# 2_waffling60-MX_matrix.net
KiCad netlist of a schematic drawn in Altium Designer
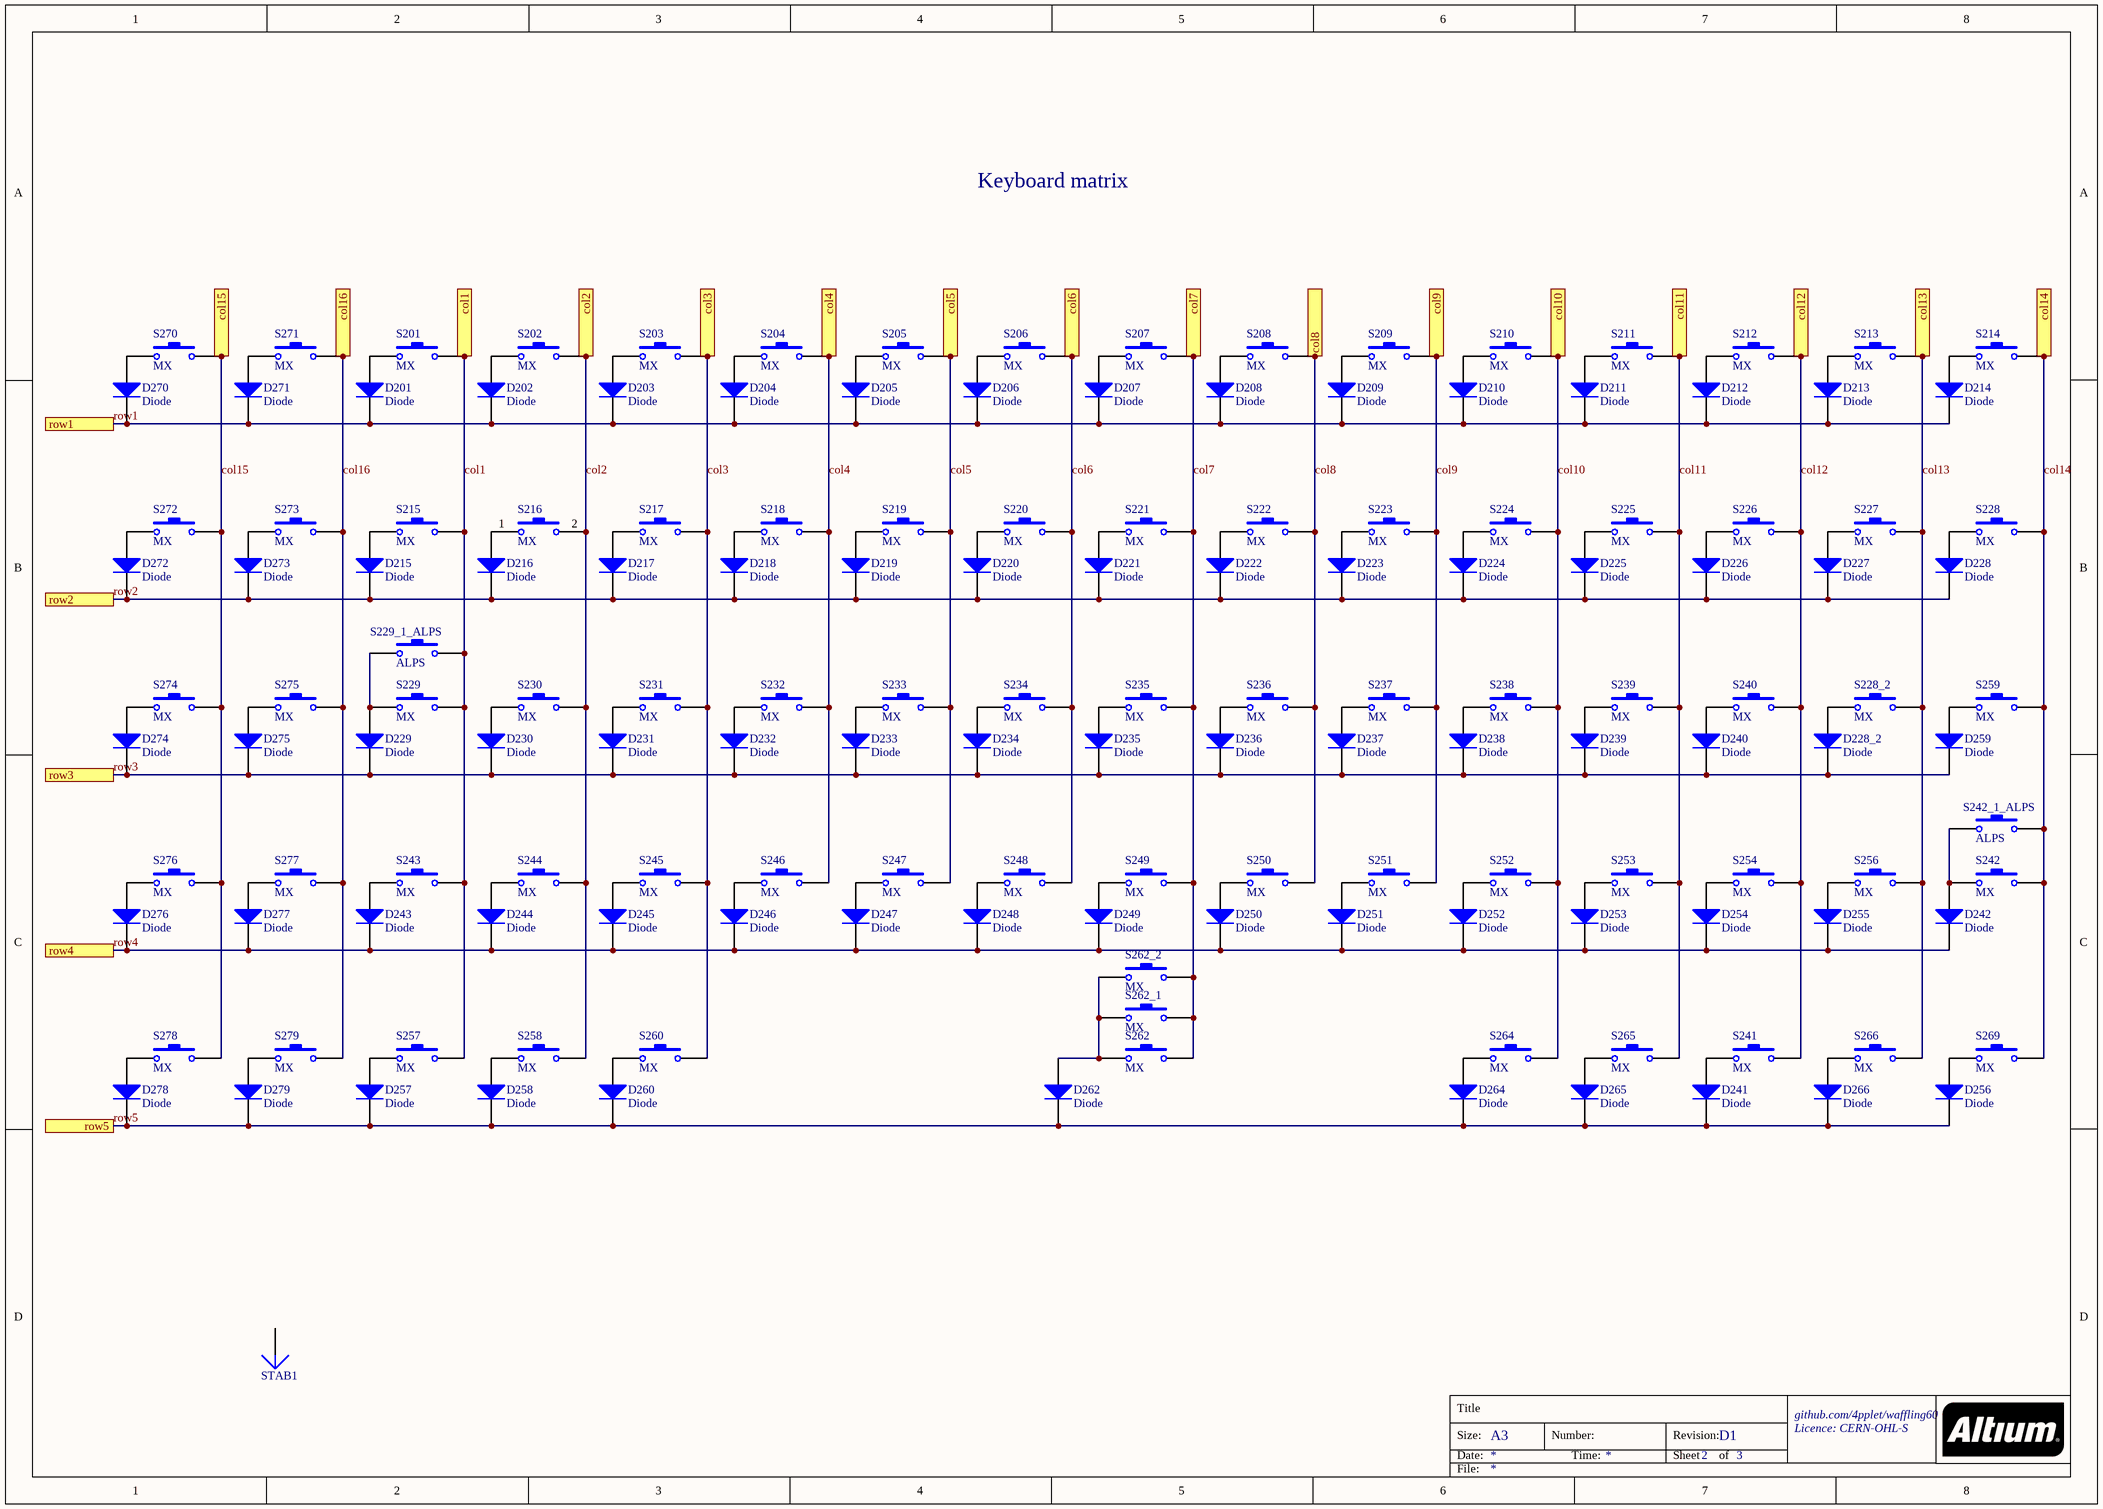
[diagram p0: 2_waffling60-MX_matrix.SchDoc]

(export (version "E")
  (design (tool "Eeschema 10.0.6"))
  (components
    (comp (ref "D201")
      (value "Diode")
      (footprint "SOD-123")
      (description "Default Diode")
      (fields (field (name "LCSC PART #") "C81598") (field (name "MRF.PART") "1N4148W"))
      (libsource (lib "Miscellaneous Devices") (part "Diode"))
    )
    (comp (ref "D202")
      (value "Diode")
      (footprint "SOD-123")
      (description "Default Diode")
      (fields (field (name "LCSC PART #") "C81598") (field (name "MRF.PART") "1N4148W"))
      (libsource (lib "Miscellaneous Devices") (part "Diode"))
    )
    (comp (ref "D203")
      (value "Diode")
      (footprint "SOD-123")
      (description "Default Diode")
      (fields (field (name "LCSC PART #") "C81598") (field (name "MRF.PART") "1N4148W"))
      (libsource (lib "Miscellaneous Devices") (part "Diode"))
    )
    (comp (ref "D204")
      (value "Diode")
      (footprint "SOD-123")
      (description "Default Diode")
      (fields (field (name "LCSC PART #") "C81598") (field (name "MRF.PART") "1N4148W"))
      (libsource (lib "Miscellaneous Devices") (part "Diode"))
    )
    (comp (ref "D205")
      (value "Diode")
      (footprint "SOD-123")
      (description "Default Diode")
      (fields (field (name "LCSC PART #") "C81598") (field (name "MRF.PART") "1N4148W"))
      (libsource (lib "Miscellaneous Devices") (part "Diode"))
    )
    (comp (ref "D206")
      (value "Diode")
      (footprint "SOD-123")
      (description "Default Diode")
      (fields (field (name "LCSC PART #") "C81598") (field (name "MRF.PART") "1N4148W"))
      (libsource (lib "Miscellaneous Devices") (part "Diode"))
    )
    (comp (ref "D207")
      (value "Diode")
      (footprint "SOD-123")
      (description "Default Diode")
      (fields (field (name "LCSC PART #") "C81598") (field (name "MRF.PART") "1N4148W"))
      (libsource (lib "Miscellaneous Devices") (part "Diode"))
    )
    (comp (ref "D208")
      (value "Diode")
      (footprint "SOD-123")
      (description "Default Diode")
      (fields (field (name "LCSC PART #") "C81598") (field (name "MRF.PART") "1N4148W"))
      (libsource (lib "Miscellaneous Devices") (part "Diode"))
    )
    (comp (ref "D209")
      (value "Diode")
      (footprint "SOD-123")
      (description "Default Diode")
      (fields (field (name "LCSC PART #") "C81598") (field (name "MRF.PART") "1N4148W"))
      (libsource (lib "Miscellaneous Devices") (part "Diode"))
    )
    (comp (ref "D210")
      (value "Diode")
      (footprint "SOD-123")
      (description "Default Diode")
      (fields (field (name "LCSC PART #") "C81598") (field (name "MRF.PART") "1N4148W"))
      (libsource (lib "Miscellaneous Devices") (part "Diode"))
    )
    (comp (ref "D211")
      (value "Diode")
      (footprint "SOD-123")
      (description "Default Diode")
      (fields (field (name "LCSC PART #") "C81598") (field (name "MRF.PART") "1N4148W"))
      (libsource (lib "Miscellaneous Devices") (part "Diode"))
    )
    (comp (ref "D212")
      (value "Diode")
      (footprint "SOD-123")
      (description "Default Diode")
      (fields (field (name "LCSC PART #") "C81598") (field (name "MRF.PART") "1N4148W"))
      (libsource (lib "Miscellaneous Devices") (part "Diode"))
    )
    (comp (ref "D213")
      (value "Diode")
      (footprint "SOD-123")
      (description "Default Diode")
      (fields (field (name "LCSC PART #") "C81598") (field (name "MRF.PART") "1N4148W"))
      (libsource (lib "Miscellaneous Devices") (part "Diode"))
    )
    (comp (ref "D214")
      (value "Diode")
      (footprint "SOD-123")
      (description "Default Diode")
      (fields (field (name "LCSC PART #") "C81598") (field (name "MRF.PART") "1N4148W"))
      (libsource (lib "Miscellaneous Devices") (part "Diode"))
    )
    (comp (ref "D215")
      (value "Diode")
      (footprint "SOD-123")
      (description "Default Diode")
      (fields (field (name "LCSC PART #") "C81598") (field (name "MRF.PART") "1N4148W"))
      (libsource (lib "Miscellaneous Devices") (part "Diode"))
    )
    (comp (ref "D216")
      (value "Diode")
      (footprint "SOD-123")
      (description "Default Diode")
      (fields (field (name "LCSC PART #") "C81598") (field (name "MRF.PART") "1N4148W"))
      (libsource (lib "Miscellaneous Devices") (part "Diode"))
    )
    (comp (ref "D217")
      (value "Diode")
      (footprint "SOD-123")
      (description "Default Diode")
      (fields (field (name "LCSC PART #") "C81598") (field (name "MRF.PART") "1N4148W"))
      (libsource (lib "Miscellaneous Devices") (part "Diode"))
    )
    (comp (ref "D218")
      (value "Diode")
      (footprint "SOD-123")
      (description "Default Diode")
      (fields (field (name "LCSC PART #") "C81598") (field (name "MRF.PART") "1N4148W"))
      (libsource (lib "Miscellaneous Devices") (part "Diode"))
    )
    (comp (ref "D219")
      (value "Diode")
      (footprint "SOD-123")
      (description "Default Diode")
      (fields (field (name "LCSC PART #") "C81598") (field (name "MRF.PART") "1N4148W"))
      (libsource (lib "Miscellaneous Devices") (part "Diode"))
    )
    (comp (ref "D220")
      (value "Diode")
      (footprint "SOD-123")
      (description "Default Diode")
      (fields (field (name "LCSC PART #") "C81598") (field (name "MRF.PART") "1N4148W"))
      (libsource (lib "Miscellaneous Devices") (part "Diode"))
    )
    (comp (ref "D221")
      (value "Diode")
      (footprint "SOD-123")
      (description "Default Diode")
      (fields (field (name "LCSC PART #") "C81598") (field (name "MRF.PART") "1N4148W"))
      (libsource (lib "Miscellaneous Devices") (part "Diode"))
    )
    (comp (ref "D222")
      (value "Diode")
      (footprint "SOD-123")
      (description "Default Diode")
      (fields (field (name "LCSC PART #") "C81598") (field (name "MRF.PART") "1N4148W"))
      (libsource (lib "Miscellaneous Devices") (part "Diode"))
    )
    (comp (ref "D223")
      (value "Diode")
      (footprint "SOD-123")
      (description "Default Diode")
      (fields (field (name "LCSC PART #") "C81598") (field (name "MRF.PART") "1N4148W"))
      (libsource (lib "Miscellaneous Devices") (part "Diode"))
    )
    (comp (ref "D224")
      (value "Diode")
      (footprint "SOD-123")
      (description "Default Diode")
      (fields (field (name "LCSC PART #") "C81598") (field (name "MRF.PART") "1N4148W"))
      (libsource (lib "Miscellaneous Devices") (part "Diode"))
    )
    (comp (ref "D225")
      (value "Diode")
      (footprint "SOD-123")
      (description "Default Diode")
      (fields (field (name "LCSC PART #") "C81598") (field (name "MRF.PART") "1N4148W"))
      (libsource (lib "Miscellaneous Devices") (part "Diode"))
    )
    (comp (ref "D226")
      (value "Diode")
      (footprint "SOD-123")
      (description "Default Diode")
      (fields (field (name "LCSC PART #") "C81598") (field (name "MRF.PART") "1N4148W"))
      (libsource (lib "Miscellaneous Devices") (part "Diode"))
    )
    (comp (ref "D227")
      (value "Diode")
      (footprint "SOD-123")
      (description "Default Diode")
      (fields (field (name "LCSC PART #") "C81598") (field (name "MRF.PART") "1N4148W"))
      (libsource (lib "Miscellaneous Devices") (part "Diode"))
    )
    (comp (ref "D228")
      (value "Diode")
      (footprint "SOD-123")
      (description "Default Diode")
      (fields (field (name "LCSC PART #") "C81598") (field (name "MRF.PART") "1N4148W"))
      (libsource (lib "Miscellaneous Devices") (part "Diode"))
    )
    (comp (ref "D228_2")
      (value "Diode")
      (footprint "SOD-123")
      (description "Default Diode")
      (fields (field (name "LCSC PART #") "C81598") (field (name "MRF.PART") "1N4148W"))
      (libsource (lib "Miscellaneous Devices") (part "Diode"))
    )
    (comp (ref "D229")
      (value "Diode")
      (footprint "SOD-123")
      (description "Default Diode")
      (fields (field (name "LCSC PART #") "C81598") (field (name "MRF.PART") "1N4148W"))
      (libsource (lib "Miscellaneous Devices") (part "Diode"))
    )
    (comp (ref "D230")
      (value "Diode")
      (footprint "SOD-123")
      (description "Default Diode")
      (fields (field (name "LCSC PART #") "C81598") (field (name "MRF.PART") "1N4148W"))
      (libsource (lib "Miscellaneous Devices") (part "Diode"))
    )
    (comp (ref "D231")
      (value "Diode")
      (footprint "SOD-123")
      (description "Default Diode")
      (fields (field (name "LCSC PART #") "C81598") (field (name "MRF.PART") "1N4148W"))
      (libsource (lib "Miscellaneous Devices") (part "Diode"))
    )
    (comp (ref "D232")
      (value "Diode")
      (footprint "SOD-123")
      (description "Default Diode")
      (fields (field (name "LCSC PART #") "C81598") (field (name "MRF.PART") "1N4148W"))
      (libsource (lib "Miscellaneous Devices") (part "Diode"))
    )
    (comp (ref "D233")
      (value "Diode")
      (footprint "SOD-123")
      (description "Default Diode")
      (fields (field (name "LCSC PART #") "C81598") (field (name "MRF.PART") "1N4148W"))
      (libsource (lib "Miscellaneous Devices") (part "Diode"))
    )
    (comp (ref "D234")
      (value "Diode")
      (footprint "SOD-123")
      (description "Default Diode")
      (fields (field (name "LCSC PART #") "C81598") (field (name "MRF.PART") "1N4148W"))
      (libsource (lib "Miscellaneous Devices") (part "Diode"))
    )
    (comp (ref "D235")
      (value "Diode")
      (footprint "SOD-123")
      (description "Default Diode")
      (fields (field (name "LCSC PART #") "C81598") (field (name "MRF.PART") "1N4148W"))
      (libsource (lib "Miscellaneous Devices") (part "Diode"))
    )
    (comp (ref "D236")
      (value "Diode")
      (footprint "SOD-123")
      (description "Default Diode")
      (fields (field (name "LCSC PART #") "C81598") (field (name "MRF.PART") "1N4148W"))
      (libsource (lib "Miscellaneous Devices") (part "Diode"))
    )
    (comp (ref "D237")
      (value "Diode")
      (footprint "SOD-123")
      (description "Default Diode")
      (fields (field (name "LCSC PART #") "C81598") (field (name "MRF.PART") "1N4148W"))
      (libsource (lib "Miscellaneous Devices") (part "Diode"))
    )
    (comp (ref "D238")
      (value "Diode")
      (footprint "SOD-123")
      (description "Default Diode")
      (fields (field (name "LCSC PART #") "C81598") (field (name "MRF.PART") "1N4148W"))
      (libsource (lib "Miscellaneous Devices") (part "Diode"))
    )
    (comp (ref "D239")
      (value "Diode")
      (footprint "SOD-123")
      (description "Default Diode")
      (fields (field (name "LCSC PART #") "C81598") (field (name "MRF.PART") "1N4148W"))
      (libsource (lib "Miscellaneous Devices") (part "Diode"))
    )
    (comp (ref "D240")
      (value "Diode")
      (footprint "SOD-123")
      (description "Default Diode")
      (fields (field (name "LCSC PART #") "C81598") (field (name "MRF.PART") "1N4148W"))
      (libsource (lib "Miscellaneous Devices") (part "Diode"))
    )
    (comp (ref "D241")
      (value "Diode")
      (footprint "SOD-123")
      (description "Default Diode")
      (fields (field (name "LCSC PART #") "C81598") (field (name "MRF.PART") "1N4148W"))
      (libsource (lib "Miscellaneous Devices") (part "Diode"))
    )
    (comp (ref "D242")
      (value "Diode")
      (footprint "SOD-123")
      (description "Default Diode")
      (fields (field (name "LCSC PART #") "C81598") (field (name "MRF.PART") "1N4148W"))
      (libsource (lib "Miscellaneous Devices") (part "Diode"))
    )
    (comp (ref "D243")
      (value "Diode")
      (footprint "SOD-123")
      (description "Default Diode")
      (fields (field (name "LCSC PART #") "C81598") (field (name "MRF.PART") "1N4148W"))
      (libsource (lib "Miscellaneous Devices") (part "Diode"))
    )
    (comp (ref "D244")
      (value "Diode")
      (footprint "SOD-123")
      (description "Default Diode")
      (fields (field (name "LCSC PART #") "C81598") (field (name "MRF.PART") "1N4148W"))
      (libsource (lib "Miscellaneous Devices") (part "Diode"))
    )
    (comp (ref "D245")
      (value "Diode")
      (footprint "SOD-123")
      (description "Default Diode")
      (fields (field (name "LCSC PART #") "C81598") (field (name "MRF.PART") "1N4148W"))
      (libsource (lib "Miscellaneous Devices") (part "Diode"))
    )
    (comp (ref "D246")
      (value "Diode")
      (footprint "SOD-123")
      (description "Default Diode")
      (fields (field (name "LCSC PART #") "C81598") (field (name "MRF.PART") "1N4148W"))
      (libsource (lib "Miscellaneous Devices") (part "Diode"))
    )
    (comp (ref "D247")
      (value "Diode")
      (footprint "SOD-123")
      (description "Default Diode")
      (fields (field (name "LCSC PART #") "C81598") (field (name "MRF.PART") "1N4148W"))
      (libsource (lib "Miscellaneous Devices") (part "Diode"))
    )
    (comp (ref "D248")
      (value "Diode")
      (footprint "SOD-123")
      (description "Default Diode")
      (fields (field (name "LCSC PART #") "C81598") (field (name "MRF.PART") "1N4148W"))
      (libsource (lib "Miscellaneous Devices") (part "Diode"))
    )
    (comp (ref "D249")
      (value "Diode")
      (footprint "SOD-123")
      (description "Default Diode")
      (fields (field (name "LCSC PART #") "C81598") (field (name "MRF.PART") "1N4148W"))
      (libsource (lib "Miscellaneous Devices") (part "Diode"))
    )
    (comp (ref "D250")
      (value "Diode")
      (footprint "SOD-123")
      (description "Default Diode")
      (fields (field (name "LCSC PART #") "C81598") (field (name "MRF.PART") "1N4148W"))
      (libsource (lib "Miscellaneous Devices") (part "Diode"))
    )
    (comp (ref "D251")
      (value "Diode")
      (footprint "SOD-123")
      (description "Default Diode")
      (fields (field (name "LCSC PART #") "C81598") (field (name "MRF.PART") "1N4148W"))
      (libsource (lib "Miscellaneous Devices") (part "Diode"))
    )
    (comp (ref "D252")
      (value "Diode")
      (footprint "SOD-123")
      (description "Default Diode")
      (fields (field (name "LCSC PART #") "C81598") (field (name "MRF.PART") "1N4148W"))
      (libsource (lib "Miscellaneous Devices") (part "Diode"))
    )
    (comp (ref "D253")
      (value "Diode")
      (footprint "SOD-123")
      (description "Default Diode")
      (fields (field (name "LCSC PART #") "C81598") (field (name "MRF.PART") "1N4148W"))
      (libsource (lib "Miscellaneous Devices") (part "Diode"))
    )
    (comp (ref "D254")
      (value "Diode")
      (footprint "SOD-123")
      (description "Default Diode")
      (fields (field (name "LCSC PART #") "C81598") (field (name "MRF.PART") "1N4148W"))
      (libsource (lib "Miscellaneous Devices") (part "Diode"))
    )
    (comp (ref "D255")
      (value "Diode")
      (footprint "SOD-123")
      (description "Default Diode")
      (fields (field (name "LCSC PART #") "C81598") (field (name "MRF.PART") "1N4148W"))
      (libsource (lib "Miscellaneous Devices") (part "Diode"))
    )
    (comp (ref "D256")
      (value "Diode")
      (footprint "SOD-123")
      (description "Default Diode")
      (fields (field (name "LCSC PART #") "C81598") (field (name "MRF.PART") "1N4148W"))
      (libsource (lib "Miscellaneous Devices") (part "Diode"))
    )
    (comp (ref "D257")
      (value "Diode")
      (footprint "SOD-123")
      (description "Default Diode")
      (fields (field (name "LCSC PART #") "C81598") (field (name "MRF.PART") "1N4148W"))
      (libsource (lib "Miscellaneous Devices") (part "Diode"))
    )
    (comp (ref "D258")
      (value "Diode")
      (footprint "SOD-123")
      (description "Default Diode")
      (fields (field (name "LCSC PART #") "C81598") (field (name "MRF.PART") "1N4148W"))
      (libsource (lib "Miscellaneous Devices") (part "Diode"))
    )
    (comp (ref "D259")
      (value "Diode")
      (footprint "SOD-123")
      (description "Default Diode")
      (fields (field (name "LCSC PART #") "C81598") (field (name "MRF.PART") "1N4148W"))
      (libsource (lib "Miscellaneous Devices") (part "Diode"))
    )
    (comp (ref "D260")
      (value "Diode")
      (footprint "SOD-123")
      (description "Default Diode")
      (fields (field (name "LCSC PART #") "C81598") (field (name "MRF.PART") "1N4148W"))
      (libsource (lib "Miscellaneous Devices") (part "Diode"))
    )
    (comp (ref "D262")
      (value "Diode")
      (footprint "SOD-123")
      (description "Default Diode")
      (fields (field (name "LCSC PART #") "C81598") (field (name "MRF.PART") "1N4148W"))
      (libsource (lib "Miscellaneous Devices") (part "Diode"))
    )
    (comp (ref "D264")
      (value "Diode")
      (footprint "SOD-123")
      (description "Default Diode")
      (fields (field (name "LCSC PART #") "C81598") (field (name "MRF.PART") "1N4148W"))
      (libsource (lib "Miscellaneous Devices") (part "Diode"))
    )
    (comp (ref "D265")
      (value "Diode")
      (footprint "SOD-123")
      (description "Default Diode")
      (fields (field (name "LCSC PART #") "C81598") (field (name "MRF.PART") "1N4148W"))
      (libsource (lib "Miscellaneous Devices") (part "Diode"))
    )
    (comp (ref "D266")
      (value "Diode")
      (footprint "SOD-123")
      (description "Default Diode")
      (fields (field (name "LCSC PART #") "C81598") (field (name "MRF.PART") "1N4148W"))
      (libsource (lib "Miscellaneous Devices") (part "Diode"))
    )
    (comp (ref "D270")
      (value "Diode")
      (footprint "SOD-123")
      (description "Default Diode")
      (fields (field (name "LCSC PART #") "C81598") (field (name "MRF.PART") "1N4148W"))
      (libsource (lib "Miscellaneous Devices") (part "Diode"))
    )
    (comp (ref "D271")
      (value "Diode")
      (footprint "SOD-123")
      (description "Default Diode")
      (fields (field (name "LCSC PART #") "C81598") (field (name "MRF.PART") "1N4148W"))
      (libsource (lib "Miscellaneous Devices") (part "Diode"))
    )
    (comp (ref "D272")
      (value "Diode")
      (footprint "SOD-123")
      (description "Default Diode")
      (fields (field (name "LCSC PART #") "C81598") (field (name "MRF.PART") "1N4148W"))
      (libsource (lib "Miscellaneous Devices") (part "Diode"))
    )
    (comp (ref "D273")
      (value "Diode")
      (footprint "SOD-123")
      (description "Default Diode")
      (fields (field (name "LCSC PART #") "C81598") (field (name "MRF.PART") "1N4148W"))
      (libsource (lib "Miscellaneous Devices") (part "Diode"))
    )
    (comp (ref "D274")
      (value "Diode")
      (footprint "SOD-123")
      (description "Default Diode")
      (fields (field (name "LCSC PART #") "C81598") (field (name "MRF.PART") "1N4148W"))
      (libsource (lib "Miscellaneous Devices") (part "Diode"))
    )
    (comp (ref "D275")
      (value "Diode")
      (footprint "SOD-123")
      (description "Default Diode")
      (fields (field (name "LCSC PART #") "C81598") (field (name "MRF.PART") "1N4148W"))
      (libsource (lib "Miscellaneous Devices") (part "Diode"))
    )
    (comp (ref "D276")
      (value "Diode")
      (footprint "SOD-123")
      (description "Default Diode")
      (fields (field (name "LCSC PART #") "C81598") (field (name "MRF.PART") "1N4148W"))
      (libsource (lib "Miscellaneous Devices") (part "Diode"))
    )
    (comp (ref "D277")
      (value "Diode")
      (footprint "SOD-123")
      (description "Default Diode")
      (fields (field (name "LCSC PART #") "C81598") (field (name "MRF.PART") "1N4148W"))
      (libsource (lib "Miscellaneous Devices") (part "Diode"))
    )
    (comp (ref "D278")
      (value "Diode")
      (footprint "SOD-123")
      (description "Default Diode")
      (fields (field (name "LCSC PART #") "C81598") (field (name "MRF.PART") "1N4148W"))
      (libsource (lib "Miscellaneous Devices") (part "Diode"))
    )
    (comp (ref "D279")
      (value "Diode")
      (footprint "SOD-123")
      (description "Default Diode")
      (fields (field (name "LCSC PART #") "C81598") (field (name "MRF.PART") "1N4148W"))
      (libsource (lib "Miscellaneous Devices") (part "Diode"))
    )
    (comp (ref "S201")
      (value "MX")
      (footprint "MX_ALPS-switch switched pol")
      (description "Switch")
      (libsource (lib "Miscellaneous Devices") (part "SW-PB"))
    )
    (comp (ref "S202")
      (value "MX")
      (footprint "MX_ALPS-switch - duplicate")
      (description "Switch")
      (libsource (lib "") (part "SW-PB_1"))
    )
    (comp (ref "S203")
      (value "MX")
      (footprint "MX_ALPS-switch switched pol")
      (description "Switch")
      (libsource (lib "Miscellaneous Devices") (part "SW-PB"))
    )
    (comp (ref "S204")
      (value "MX")
      (footprint "MX_ALPS-switch switched pol")
      (description "Switch")
      (libsource (lib "Miscellaneous Devices") (part "SW-PB"))
    )
    (comp (ref "S205")
      (value "MX")
      (footprint "MX_ALPS-switch switched pol")
      (description "Switch")
      (libsource (lib "Miscellaneous Devices") (part "SW-PB"))
    )
    (comp (ref "S206")
      (value "MX")
      (footprint "MX_ALPS-switch switched pol")
      (description "Switch")
      (libsource (lib "Miscellaneous Devices") (part "SW-PB"))
    )
    (comp (ref "S207")
      (value "MX")
      (footprint "MX_ALPS-switch switched pol")
      (description "Switch")
      (libsource (lib "Miscellaneous Devices") (part "SW-PB"))
    )
    (comp (ref "S208")
      (value "MX")
      (footprint "MX_ALPS-switch switched pol")
      (description "Switch")
      (libsource (lib "Miscellaneous Devices") (part "SW-PB"))
    )
    (comp (ref "S209")
      (value "MX")
      (footprint "MX_ALPS-switch switched pol")
      (description "Switch")
      (libsource (lib "Miscellaneous Devices") (part "SW-PB"))
    )
    (comp (ref "S210")
      (value "MX")
      (footprint "MX_ALPS-switch switched pol")
      (description "Switch")
      (libsource (lib "Miscellaneous Devices") (part "SW-PB"))
    )
    (comp (ref "S211")
      (value "MX")
      (footprint "MX_ALPS-switch switched pol")
      (description "Switch")
      (libsource (lib "Miscellaneous Devices") (part "SW-PB"))
    )
    (comp (ref "S212")
      (value "MX")
      (footprint "MX_ALPS-switch switched pol")
      (description "Switch")
      (libsource (lib "Miscellaneous Devices") (part "SW-PB"))
    )
    (comp (ref "S213")
      (value "MX")
      (footprint "MX_ALPS-switch switched pol")
      (description "Switch")
      (libsource (lib "Miscellaneous Devices") (part "SW-PB"))
    )
    (comp (ref "S214")
      (value "MX")
      (footprint "MX_ALPS-switch - duplicate")
      (description "Switch")
      (libsource (lib "Miscellaneous Devices") (part "SW-PB"))
    )
    (comp (ref "S215")
      (value "MX")
      (footprint "MX_ALPS-switch switched pol")
      (description "TAB")
      (libsource (lib "Miscellaneous Devices") (part "SW-PB"))
    )
    (comp (ref "S216")
      (value "MX")
      (footprint "MX_ALPS-switch - duplicate")
      (description "Switch")
      (libsource (lib "") (part "SW-PB_2"))
    )
    (comp (ref "S217")
      (value "MX")
      (footprint "MX_ALPS-switch switched pol")
      (description "Switch")
      (libsource (lib "Miscellaneous Devices") (part "SW-PB"))
    )
    (comp (ref "S218")
      (value "MX")
      (footprint "MX_ALPS-switch switched pol")
      (description "Switch")
      (libsource (lib "Miscellaneous Devices") (part "SW-PB"))
    )
    (comp (ref "S219")
      (value "MX")
      (footprint "MX_ALPS-switch switched pol")
      (description "Switch")
      (libsource (lib "Miscellaneous Devices") (part "SW-PB"))
    )
    (comp (ref "S220")
      (value "MX")
      (footprint "MX_ALPS-switch - duplicate")
      (description "Switch")
      (libsource (lib "Miscellaneous Devices") (part "SW-PB"))
    )
    (comp (ref "S221")
      (value "MX")
      (footprint "MX_ALPS-switch switched pol")
      (description "Switch")
      (libsource (lib "Miscellaneous Devices") (part "SW-PB"))
    )
    (comp (ref "S222")
      (value "MX")
      (footprint "MX_ALPS-switch - duplicate")
      (description "Switch")
      (libsource (lib "Miscellaneous Devices") (part "SW-PB"))
    )
    (comp (ref "S223")
      (value "MX")
      (footprint "MX_ALPS-switch switched pol")
      (description "Switch")
      (libsource (lib "Miscellaneous Devices") (part "SW-PB"))
    )
    (comp (ref "S224")
      (value "MX")
      (footprint "MX_ALPS-switch switched pol")
      (description "Switch")
      (libsource (lib "Miscellaneous Devices") (part "SW-PB"))
    )
    (comp (ref "S225")
      (value "MX")
      (footprint "MX_ALPS-switch switched pol")
      (description "Switch")
      (libsource (lib "Miscellaneous Devices") (part "SW-PB"))
    )
    (comp (ref "S226")
      (value "MX")
      (footprint "MX_ALPS-switch - duplicate")
      (description "Switch")
      (libsource (lib "Miscellaneous Devices") (part "SW-PB"))
    )
    (comp (ref "S227")
      (value "MX")
      (footprint "MX_ALPS-switch - duplicate")
      (description "Switch")
      (libsource (lib "Miscellaneous Devices") (part "SW-PB"))
    )
    (comp (ref "S228")
      (value "MX")
      (footprint "mx_alps - 1.5U")
      (description "Switch")
      (libsource (lib "Miscellaneous Devices") (part "SW-PB"))
    )
    (comp (ref "S228_2")
      (value "MX")
      (footprint "MX_ALPS-switch - duplicate")
      (description "Switch")
      (libsource (lib "Miscellaneous Devices") (part "SW-PB"))
    )
    (comp (ref "S229")
      (value "MX")
      (footprint "mx_alps - CAPS")
      (description "Switch")
      (libsource (lib "Miscellaneous Devices") (part "SW-PB"))
    )
    (comp (ref "S229_1_ALPS")
      (value "ALPS")
      (footprint "ALPS-switch - 1.5U")
      (description "Switch")
      (libsource (lib "Miscellaneous Devices") (part "SW-PB"))
    )
    (comp (ref "S230")
      (value "MX")
      (footprint "MX_ALPS-switch - duplicate")
      (description "Switch")
      (libsource (lib "Miscellaneous Devices") (part "SW-PB"))
    )
    (comp (ref "S231")
      (value "MX")
      (footprint "MX_ALPS-switch switched pol")
      (description "Switch")
      (libsource (lib "Miscellaneous Devices") (part "SW-PB"))
    )
    (comp (ref "S232")
      (value "MX")
      (footprint "MX_ALPS-switch switched pol")
      (description "Switch")
      (libsource (lib "Miscellaneous Devices") (part "SW-PB"))
    )
    (comp (ref "S233")
      (value "MX")
      (footprint "MX_ALPS-switch switched pol")
      (description "Switch")
      (libsource (lib "Miscellaneous Devices") (part "SW-PB"))
    )
    (comp (ref "S234")
      (value "MX")
      (footprint "MX_ALPS-switch switched pol")
      (description "Switch")
      (libsource (lib "Miscellaneous Devices") (part "SW-PB"))
    )
    (comp (ref "S235")
      (value "MX")
      (footprint "MX_ALPS-switch switched pol")
      (description "Switch")
      (libsource (lib "Miscellaneous Devices") (part "SW-PB"))
    )
    (comp (ref "S236")
      (value "MX")
      (footprint "MX_ALPS-switch switched pol")
      (description "Switch")
      (libsource (lib "Miscellaneous Devices") (part "SW-PB"))
    )
    (comp (ref "S237")
      (value "MX")
      (footprint "MX_ALPS-switch switched pol")
      (description "Switch")
      (libsource (lib "Miscellaneous Devices") (part "SW-PB"))
    )
    (comp (ref "S238")
      (value "MX")
      (footprint "MX_ALPS-switch switched pol")
      (description "Switch")
      (libsource (lib "Miscellaneous Devices") (part "SW-PB"))
    )
    (comp (ref "S239")
      (value "MX")
      (footprint "MX_ALPS-switch switched pol")
      (description "Switch")
      (libsource (lib "Miscellaneous Devices") (part "SW-PB"))
    )
    (comp (ref "S240")
      (value "MX")
      (footprint "MX_ALPS-switch switched pol")
      (description "Switch")
      (libsource (lib "Miscellaneous Devices") (part "SW-PB"))
    )
    (comp (ref "S241")
      (value "MX")
      (footprint "mx_alps - 1u MOD-R")
      (description "Switch")
      (libsource (lib "Miscellaneous Devices") (part "SW-PB"))
    )
    (comp (ref "S242")
      (value "MX")
      (footprint "mx_alps - Enter - Rotated Stab")
      (description "Switch")
      (libsource (lib "Miscellaneous Devices") (part "SW-PB"))
    )
    (comp (ref "S242_1_ALPS")
      (value "ALPS")
      (footprint "ALPS-switch - 1.5U")
      (description "Switch")
      (libsource (lib "") (part "SW-PB_1"))
    )
    (comp (ref "S243")
      (value "MX")
      (footprint "mx_alps - Left shift")
      (description "Switch")
      (libsource (lib "Miscellaneous Devices") (part "SW-PB"))
    )
    (comp (ref "S244")
      (value "MX")
      (footprint "MX_ALPS-switch")
      (description "Switch")
      (libsource (lib "Miscellaneous Devices") (part "SW-PB"))
    )
    (comp (ref "S245")
      (value "MX")
      (footprint "MX_ALPS-switch switched pol")
      (description "Switch")
      (libsource (lib "Miscellaneous Devices") (part "SW-PB"))
    )
    (comp (ref "S246")
      (value "MX")
      (footprint "MX_ALPS-switch switched pol")
      (description "Switch")
      (libsource (lib "Miscellaneous Devices") (part "SW-PB"))
    )
    (comp (ref "S247")
      (value "MX")
      (footprint "MX_ALPS-switch switched pol")
      (description "Switch")
      (libsource (lib "Miscellaneous Devices") (part "SW-PB"))
    )
    (comp (ref "S248")
      (value "MX")
      (footprint "MX_ALPS-switch switched pol")
      (description "Switch")
      (libsource (lib "Miscellaneous Devices") (part "SW-PB"))
    )
    (comp (ref "S249")
      (value "MX")
      (footprint "MX_ALPS-switch switched pol")
      (description "Switch")
      (libsource (lib "Miscellaneous Devices") (part "SW-PB"))
    )
    (comp (ref "S250")
      (value "MX")
      (footprint "MX_ALPS-switch switched pol")
      (description "Switch")
      (libsource (lib "Miscellaneous Devices") (part "SW-PB"))
    )
    (comp (ref "S251")
      (value "MX")
      (footprint "MX_ALPS-switch switched pol")
      (description "Switch")
      (libsource (lib "Miscellaneous Devices") (part "SW-PB"))
    )
    (comp (ref "S252")
      (value "MX")
      (footprint "MX_ALPS-switch switched pol")
      (description "Switch")
      (libsource (lib "Miscellaneous Devices") (part "SW-PB"))
    )
    (comp (ref "S253")
      (value "MX")
      (footprint "MX_ALPS-switch switched pol")
      (description "Switch")
      (libsource (lib "Miscellaneous Devices") (part "SW-PB"))
    )
    (comp (ref "S254")
      (value "MX")
      (footprint "MX_ALPS-switch switched pol")
      (description "Switch")
      (libsource (lib "Miscellaneous Devices") (part "SW-PB"))
    )
    (comp (ref "S256")
      (value "MX")
      (footprint "mx_alps- right shift")
      (description "Switch")
      (libsource (lib "Miscellaneous Devices") (part "SW-PB"))
    )
    (comp (ref "S257")
      (value "MX")
      (footprint "mx_alps- 1.5u MOD-L")
      (description "Switch")
      (libsource (lib "Miscellaneous Devices") (part "SW-PB"))
    )
    (comp (ref "S258")
      (value "MX")
      (footprint "mx_alps - 1u MOD-L")
      (description "Switch")
      (libsource (lib "Miscellaneous Devices") (part "SW-PB"))
    )
    (comp (ref "S259")
      (value "MX")
      (footprint "mx_alps - backspace")
      (description "Switch")
      (libsource (lib "Miscellaneous Devices") (part "SW-PB"))
    )
    (comp (ref "S260")
      (value "MX")
      (footprint "mx_alps- 1.5u MOD-L")
      (description "Switch")
      (libsource (lib "Miscellaneous Devices") (part "SW-PB"))
    )
    (comp (ref "S262")
      (value "MX")
      (footprint "MX-switch - Space_7U+6.27U")
      (description "Switch")
      (libsource (lib "Miscellaneous Devices") (part "SW-PB"))
    )
    (comp (ref "S262_1")
      (value "MX")
      (footprint "MX_ALPS-switch")
      (description "Switch")
      (libsource (lib "") (part "SW-PB_1"))
    )
    (comp (ref "S262_2")
      (value "MX")
      (footprint "MX_ALPS-switch")
      (description "Switch")
      (libsource (lib "Miscellaneous Devices") (part "SW-PB"))
    )
    (comp (ref "S264")
      (value "MX")
      (footprint "MX_ALPS-switch switched pol")
      (description "Switch")
      (libsource (lib "Miscellaneous Devices") (part "SW-PB"))
    )
    (comp (ref "S265")
      (value "MX")
      (footprint "mx_alps - 1.5u MOD-R")
      (description "Switch")
      (libsource (lib "Miscellaneous Devices") (part "SW-PB"))
    )
    (comp (ref "S266")
      (value "MX")
      (footprint "mx_alps - 1.5u MOD-R")
      (description "Switch")
      (libsource (lib "Miscellaneous Devices") (part "SW-PB"))
    )
    (comp (ref "S269")
      (value "MX")
      (footprint "MX_ALPS-switch - duplicate")
      (description "Switch")
      (libsource (lib "Miscellaneous Devices") (part "SW-PB"))
    )
    (comp (ref "S270")
      (value "MX")
      (footprint "MX_ALPS-switch switched pol")
      (description "Switch")
      (libsource (lib "Miscellaneous Devices") (part "SW-PB"))
    )
    (comp (ref "S271")
      (value "MX")
      (footprint "MX_ALPS-switch switched pol")
      (description "Switch")
      (libsource (lib "Miscellaneous Devices") (part "SW-PB"))
    )
    (comp (ref "S272")
      (value "MX")
      (footprint "MX_ALPS-switch switched pol")
      (description "Switch")
      (libsource (lib "Miscellaneous Devices") (part "SW-PB"))
    )
    (comp (ref "S273")
      (value "MX")
      (footprint "MX_ALPS-switch switched pol")
      (description "Switch")
      (libsource (lib "Miscellaneous Devices") (part "SW-PB"))
    )
    (comp (ref "S274")
      (value "MX")
      (footprint "MX_ALPS-switch switched pol")
      (description "Switch")
      (libsource (lib "Miscellaneous Devices") (part "SW-PB"))
    )
    (comp (ref "S275")
      (value "MX")
      (footprint "MX_ALPS-switch switched pol")
      (description "Switch")
      (libsource (lib "Miscellaneous Devices") (part "SW-PB"))
    )
    (comp (ref "S276")
      (value "MX")
      (footprint "MX_ALPS-switch switched pol")
      (description "Switch")
      (libsource (lib "Miscellaneous Devices") (part "SW-PB"))
    )
    (comp (ref "S277")
      (value "MX")
      (footprint "MX_ALPS-switch switched pol")
      (description "Switch")
      (libsource (lib "Miscellaneous Devices") (part "SW-PB"))
    )
    (comp (ref "S278")
      (value "MX")
      (footprint "MX_ALPS-switch switched pol")
      (description "Switch")
      (libsource (lib "Miscellaneous Devices") (part "SW-PB"))
    )
    (comp (ref "S279")
      (value "MX")
      (footprint "MX_ALPS-switch switched pol")
      (description "Switch")
      (libsource (lib "Miscellaneous Devices") (part "SW-PB"))
    )
    (comp (ref "STAB1")
      (value "Plug")
      (footprint "Stab 10U")
      (libsource (lib "Miscellaneous Connectors") (part "Plug"))
    )
  )
  (nets
    (net (code "1") (name "/col1") (class "Default")
      (node (ref "S201") (pin "2") (pinfunction "2_2") (pintype "passive"))
      (node (ref "S215") (pin "2") (pinfunction "2_2") (pintype "passive"))
      (node (ref "S229") (pin "1") (pinfunction "1_1") (pintype "passive"))
      (node (ref "S229_1_ALPS") (pin "2") (pinfunction "2_2") (pintype "passive"))
      (node (ref "S243") (pin "2") (pinfunction "2_2") (pintype "passive"))
      (node (ref "S257") (pin "1") (pinfunction "1_1") (pintype "passive"))
    )
    (net (code "2") (name "/col2") (class "Default")
      (node (ref "S202") (pin "1") (pinfunction "1_1") (pintype "passive"))
      (node (ref "S216") (pin "2") (pinfunction "2_2") (pintype "passive"))
      (node (ref "S230") (pin "2") (pinfunction "2_2") (pintype "passive"))
      (node (ref "S244") (pin "1") (pinfunction "1_1") (pintype "passive"))
      (node (ref "S258") (pin "2") (pinfunction "2_2") (pintype "passive"))
    )
    (net (code "3") (name "/col3") (class "Default")
      (node (ref "S203") (pin "2") (pinfunction "2_2") (pintype "passive"))
      (node (ref "S217") (pin "2") (pinfunction "2_2") (pintype "passive"))
      (node (ref "S231") (pin "2") (pinfunction "2_2") (pintype "passive"))
      (node (ref "S245") (pin "2") (pinfunction "2_2") (pintype "passive"))
      (node (ref "S260") (pin "2") (pinfunction "2_2") (pintype "passive"))
    )
    (net (code "4") (name "/col4") (class "Default")
      (node (ref "S204") (pin "2") (pinfunction "2_2") (pintype "passive"))
      (node (ref "S218") (pin "2") (pinfunction "2_2") (pintype "passive"))
      (node (ref "S232") (pin "2") (pinfunction "2_2") (pintype "passive"))
      (node (ref "S246") (pin "2") (pinfunction "2_2") (pintype "passive"))
    )
    (net (code "5") (name "/col5") (class "Default")
      (node (ref "S205") (pin "2") (pinfunction "2_2") (pintype "passive"))
      (node (ref "S219") (pin "2") (pinfunction "2_2") (pintype "passive"))
      (node (ref "S233") (pin "2") (pinfunction "2_2") (pintype "passive"))
      (node (ref "S247") (pin "2") (pinfunction "2_2") (pintype "passive"))
    )
    (net (code "6") (name "/col6") (class "Default")
      (node (ref "S206") (pin "2") (pinfunction "2_2") (pintype "passive"))
      (node (ref "S220") (pin "2") (pinfunction "2_2") (pintype "passive"))
      (node (ref "S234") (pin "2") (pinfunction "2_2") (pintype "passive"))
      (node (ref "S248") (pin "2") (pinfunction "2_2") (pintype "passive"))
    )
    (net (code "7") (name "/col7") (class "Default")
      (node (ref "S207") (pin "2") (pinfunction "2_2") (pintype "passive"))
      (node (ref "S221") (pin "2") (pinfunction "2_2") (pintype "passive"))
      (node (ref "S235") (pin "2") (pinfunction "2_2") (pintype "passive"))
      (node (ref "S249") (pin "2") (pinfunction "2_2") (pintype "passive"))
      (node (ref "S262") (pin "1") (pinfunction "1_1") (pintype "passive"))
      (node (ref "S262_1") (pin "1") (pinfunction "1_1") (pintype "passive"))
      (node (ref "S262_2") (pin "2") (pinfunction "2_2") (pintype "passive"))
    )
    (net (code "8") (name "/col8") (class "Default")
      (node (ref "S208") (pin "2") (pinfunction "2_2") (pintype "passive"))
      (node (ref "S222") (pin "2") (pinfunction "2_2") (pintype "passive"))
      (node (ref "S236") (pin "2") (pinfunction "2_2") (pintype "passive"))
      (node (ref "S250") (pin "2") (pinfunction "2_2") (pintype "passive"))
    )
    (net (code "9") (name "/col9") (class "Default")
      (node (ref "S209") (pin "2") (pinfunction "2_2") (pintype "passive"))
      (node (ref "S223") (pin "2") (pinfunction "2_2") (pintype "passive"))
      (node (ref "S237") (pin "2") (pinfunction "2_2") (pintype "passive"))
      (node (ref "S251") (pin "2") (pinfunction "2_2") (pintype "passive"))
    )
    (net (code "10") (name "/col10") (class "Default")
      (node (ref "S210") (pin "2") (pinfunction "2_2") (pintype "passive"))
      (node (ref "S224") (pin "2") (pinfunction "2_2") (pintype "passive"))
      (node (ref "S238") (pin "2") (pinfunction "2_2") (pintype "passive"))
      (node (ref "S252") (pin "2") (pinfunction "2_2") (pintype "passive"))
      (node (ref "S264") (pin "2") (pinfunction "2_2") (pintype "passive"))
    )
    (net (code "11") (name "/col11") (class "Default")
      (node (ref "S211") (pin "2") (pinfunction "2_2") (pintype "passive"))
      (node (ref "S225") (pin "2") (pinfunction "2_2") (pintype "passive"))
      (node (ref "S239") (pin "2") (pinfunction "2_2") (pintype "passive"))
      (node (ref "S253") (pin "2") (pinfunction "2_2") (pintype "passive"))
      (node (ref "S265") (pin "1") (pinfunction "1_1") (pintype "passive"))
    )
    (net (code "12") (name "/col12") (class "Default")
      (node (ref "S212") (pin "2") (pinfunction "2_2") (pintype "passive"))
      (node (ref "S226") (pin "2") (pinfunction "2_2") (pintype "passive"))
      (node (ref "S240") (pin "2") (pinfunction "2_2") (pintype "passive"))
      (node (ref "S241") (pin "1") (pinfunction "1_1") (pintype "passive"))
      (node (ref "S254") (pin "2") (pinfunction "2_2") (pintype "passive"))
    )
    (net (code "13") (name "/col13") (class "Default")
      (node (ref "S213") (pin "2") (pinfunction "2_2") (pintype "passive"))
      (node (ref "S227") (pin "2") (pinfunction "2_2") (pintype "passive"))
      (node (ref "S228_2") (pin "2") (pinfunction "2_2") (pintype "passive"))
      (node (ref "S256") (pin "2") (pinfunction "2_2") (pintype "passive"))
      (node (ref "S266") (pin "2") (pinfunction "2_2") (pintype "passive"))
    )
    (net (code "14") (name "/col14") (class "Default")
      (node (ref "S214") (pin "2") (pinfunction "2_2") (pintype "passive"))
      (node (ref "S228") (pin "2") (pinfunction "2_2") (pintype "passive"))
      (node (ref "S242") (pin "2") (pinfunction "2_2") (pintype "passive"))
      (node (ref "S242_1_ALPS") (pin "1") (pinfunction "1_1") (pintype "passive"))
      (node (ref "S259") (pin "2") (pinfunction "2_2") (pintype "passive"))
      (node (ref "S269") (pin "2") (pinfunction "2_2") (pintype "passive"))
    )
    (net (code "15") (name "/col15") (class "Default")
      (node (ref "S270") (pin "2") (pinfunction "2_2") (pintype "passive"))
      (node (ref "S272") (pin "2") (pinfunction "2_2") (pintype "passive"))
      (node (ref "S274") (pin "2") (pinfunction "2_2") (pintype "passive"))
      (node (ref "S276") (pin "2") (pinfunction "2_2") (pintype "passive"))
      (node (ref "S278") (pin "2") (pinfunction "2_2") (pintype "passive"))
    )
    (net (code "16") (name "/col16") (class "Default")
      (node (ref "S271") (pin "2") (pinfunction "2_2") (pintype "passive"))
      (node (ref "S273") (pin "2") (pinfunction "2_2") (pintype "passive"))
      (node (ref "S275") (pin "2") (pinfunction "2_2") (pintype "passive"))
      (node (ref "S277") (pin "2") (pinfunction "2_2") (pintype "passive"))
      (node (ref "S279") (pin "2") (pinfunction "2_2") (pintype "passive"))
    )
    (net (code "17") (name "/row1") (class "Default")
      (node (ref "D201") (pin "2") (pinfunction "K_2") (pintype "passive"))
      (node (ref "D202") (pin "2") (pinfunction "K_2") (pintype "passive"))
      (node (ref "D203") (pin "2") (pinfunction "K_2") (pintype "passive"))
      (node (ref "D204") (pin "2") (pinfunction "K_2") (pintype "passive"))
      (node (ref "D205") (pin "2") (pinfunction "K_2") (pintype "passive"))
      (node (ref "D206") (pin "2") (pinfunction "K_2") (pintype "passive"))
      (node (ref "D207") (pin "2") (pinfunction "K_2") (pintype "passive"))
      (node (ref "D208") (pin "2") (pinfunction "K_2") (pintype "passive"))
      (node (ref "D209") (pin "2") (pinfunction "K_2") (pintype "passive"))
      (node (ref "D210") (pin "2") (pinfunction "K_2") (pintype "passive"))
      (node (ref "D211") (pin "2") (pinfunction "K_2") (pintype "passive"))
      (node (ref "D212") (pin "2") (pinfunction "K_2") (pintype "passive"))
      (node (ref "D213") (pin "2") (pinfunction "K_2") (pintype "passive"))
      (node (ref "D214") (pin "2") (pinfunction "K_2") (pintype "passive"))
      (node (ref "D270") (pin "2") (pinfunction "K_2") (pintype "passive"))
      (node (ref "D271") (pin "2") (pinfunction "K_2") (pintype "passive"))
    )
    (net (code "18") (name "/row2") (class "Default")
      (node (ref "D215") (pin "2") (pinfunction "K_2") (pintype "passive"))
      (node (ref "D216") (pin "2") (pinfunction "K_2") (pintype "passive"))
      (node (ref "D217") (pin "2") (pinfunction "K_2") (pintype "passive"))
      (node (ref "D218") (pin "2") (pinfunction "K_2") (pintype "passive"))
      (node (ref "D219") (pin "2") (pinfunction "K_2") (pintype "passive"))
      (node (ref "D220") (pin "2") (pinfunction "K_2") (pintype "passive"))
      (node (ref "D221") (pin "2") (pinfunction "K_2") (pintype "passive"))
      (node (ref "D222") (pin "2") (pinfunction "K_2") (pintype "passive"))
      (node (ref "D223") (pin "2") (pinfunction "K_2") (pintype "passive"))
      (node (ref "D224") (pin "2") (pinfunction "K_2") (pintype "passive"))
      (node (ref "D225") (pin "2") (pinfunction "K_2") (pintype "passive"))
      (node (ref "D226") (pin "2") (pinfunction "K_2") (pintype "passive"))
      (node (ref "D227") (pin "2") (pinfunction "K_2") (pintype "passive"))
      (node (ref "D228") (pin "2") (pinfunction "K_2") (pintype "passive"))
      (node (ref "D272") (pin "2") (pinfunction "K_2") (pintype "passive"))
      (node (ref "D273") (pin "2") (pinfunction "K_2") (pintype "passive"))
    )
    (net (code "19") (name "/row3") (class "Default")
      (node (ref "D228_2") (pin "2") (pinfunction "K_2") (pintype "passive"))
      (node (ref "D229") (pin "2") (pinfunction "K_2") (pintype "passive"))
      (node (ref "D230") (pin "2") (pinfunction "K_2") (pintype "passive"))
      (node (ref "D231") (pin "2") (pinfunction "K_2") (pintype "passive"))
      (node (ref "D232") (pin "2") (pinfunction "K_2") (pintype "passive"))
      (node (ref "D233") (pin "2") (pinfunction "K_2") (pintype "passive"))
      (node (ref "D234") (pin "2") (pinfunction "K_2") (pintype "passive"))
      (node (ref "D235") (pin "2") (pinfunction "K_2") (pintype "passive"))
      (node (ref "D236") (pin "2") (pinfunction "K_2") (pintype "passive"))
      (node (ref "D237") (pin "2") (pinfunction "K_2") (pintype "passive"))
      (node (ref "D238") (pin "2") (pinfunction "K_2") (pintype "passive"))
      (node (ref "D239") (pin "2") (pinfunction "K_2") (pintype "passive"))
      (node (ref "D240") (pin "2") (pinfunction "K_2") (pintype "passive"))
      (node (ref "D259") (pin "2") (pinfunction "K_2") (pintype "passive"))
      (node (ref "D274") (pin "2") (pinfunction "K_2") (pintype "passive"))
      (node (ref "D275") (pin "2") (pinfunction "K_2") (pintype "passive"))
    )
    (net (code "20") (name "/row4") (class "Default")
      (node (ref "D242") (pin "2") (pinfunction "K_2") (pintype "passive"))
      (node (ref "D243") (pin "2") (pinfunction "K_2") (pintype "passive"))
      (node (ref "D244") (pin "2") (pinfunction "K_2") (pintype "passive"))
      (node (ref "D245") (pin "2") (pinfunction "K_2") (pintype "passive"))
      (node (ref "D246") (pin "2") (pinfunction "K_2") (pintype "passive"))
      (node (ref "D247") (pin "2") (pinfunction "K_2") (pintype "passive"))
      (node (ref "D248") (pin "2") (pinfunction "K_2") (pintype "passive"))
      (node (ref "D249") (pin "2") (pinfunction "K_2") (pintype "passive"))
      (node (ref "D250") (pin "2") (pinfunction "K_2") (pintype "passive"))
      (node (ref "D251") (pin "2") (pinfunction "K_2") (pintype "passive"))
      (node (ref "D252") (pin "2") (pinfunction "K_2") (pintype "passive"))
      (node (ref "D253") (pin "2") (pinfunction "K_2") (pintype "passive"))
      (node (ref "D254") (pin "2") (pinfunction "K_2") (pintype "passive"))
      (node (ref "D255") (pin "2") (pinfunction "K_2") (pintype "passive"))
      (node (ref "D276") (pin "2") (pinfunction "K_2") (pintype "passive"))
      (node (ref "D277") (pin "2") (pinfunction "K_2") (pintype "passive"))
    )
    (net (code "21") (name "/row5") (class "Default")
      (node (ref "D241") (pin "2") (pinfunction "K_2") (pintype "passive"))
      (node (ref "D256") (pin "2") (pinfunction "K_2") (pintype "passive"))
      (node (ref "D257") (pin "2") (pinfunction "K_2") (pintype "passive"))
      (node (ref "D258") (pin "2") (pinfunction "K_2") (pintype "passive"))
      (node (ref "D260") (pin "2") (pinfunction "K_2") (pintype "passive"))
      (node (ref "D262") (pin "2") (pinfunction "K_2") (pintype "passive"))
      (node (ref "D264") (pin "2") (pinfunction "K_2") (pintype "passive"))
      (node (ref "D265") (pin "2") (pinfunction "K_2") (pintype "passive"))
      (node (ref "D266") (pin "2") (pinfunction "K_2") (pintype "passive"))
      (node (ref "D278") (pin "2") (pinfunction "K_2") (pintype "passive"))
      (node (ref "D279") (pin "2") (pinfunction "K_2") (pintype "passive"))
    )
    (net (code "22") (name "Net-(D201-A)") (class "Default")
      (node (ref "D201") (pin "1") (pinfunction "A_1") (pintype "passive"))
      (node (ref "S201") (pin "1") (pinfunction "1_1") (pintype "passive"))
    )
    (net (code "23") (name "Net-(D202-A)") (class "Default")
      (node (ref "D202") (pin "1") (pinfunction "A_1") (pintype "passive"))
      (node (ref "S202") (pin "2") (pinfunction "2_2") (pintype "passive"))
    )
    (net (code "24") (name "Net-(D203-A)") (class "Default")
      (node (ref "D203") (pin "1") (pinfunction "A_1") (pintype "passive"))
      (node (ref "S203") (pin "1") (pinfunction "1_1") (pintype "passive"))
    )
    (net (code "25") (name "Net-(D204-A)") (class "Default")
      (node (ref "D204") (pin "1") (pinfunction "A_1") (pintype "passive"))
      (node (ref "S204") (pin "1") (pinfunction "1_1") (pintype "passive"))
    )
    (net (code "26") (name "Net-(D205-A)") (class "Default")
      (node (ref "D205") (pin "1") (pinfunction "A_1") (pintype "passive"))
      (node (ref "S205") (pin "1") (pinfunction "1_1") (pintype "passive"))
    )
    (net (code "27") (name "Net-(D206-A)") (class "Default")
      (node (ref "D206") (pin "1") (pinfunction "A_1") (pintype "passive"))
      (node (ref "S206") (pin "1") (pinfunction "1_1") (pintype "passive"))
    )
    (net (code "28") (name "Net-(D207-A)") (class "Default")
      (node (ref "D207") (pin "1") (pinfunction "A_1") (pintype "passive"))
      (node (ref "S207") (pin "1") (pinfunction "1_1") (pintype "passive"))
    )
    (net (code "29") (name "Net-(D208-A)") (class "Default")
      (node (ref "D208") (pin "1") (pinfunction "A_1") (pintype "passive"))
      (node (ref "S208") (pin "1") (pinfunction "1_1") (pintype "passive"))
    )
    (net (code "30") (name "Net-(D209-A)") (class "Default")
      (node (ref "D209") (pin "1") (pinfunction "A_1") (pintype "passive"))
      (node (ref "S209") (pin "1") (pinfunction "1_1") (pintype "passive"))
    )
    (net (code "31") (name "Net-(D210-A)") (class "Default")
      (node (ref "D210") (pin "1") (pinfunction "A_1") (pintype "passive"))
      (node (ref "S210") (pin "1") (pinfunction "1_1") (pintype "passive"))
    )
    (net (code "32") (name "Net-(D211-A)") (class "Default")
      (node (ref "D211") (pin "1") (pinfunction "A_1") (pintype "passive"))
      (node (ref "S211") (pin "1") (pinfunction "1_1") (pintype "passive"))
    )
    (net (code "33") (name "Net-(D212-A)") (class "Default")
      (node (ref "D212") (pin "1") (pinfunction "A_1") (pintype "passive"))
      (node (ref "S212") (pin "1") (pinfunction "1_1") (pintype "passive"))
    )
    (net (code "34") (name "Net-(D213-A)") (class "Default")
      (node (ref "D213") (pin "1") (pinfunction "A_1") (pintype "passive"))
      (node (ref "S213") (pin "1") (pinfunction "1_1") (pintype "passive"))
    )
    (net (code "35") (name "Net-(D214-A)") (class "Default")
      (node (ref "D214") (pin "1") (pinfunction "A_1") (pintype "passive"))
      (node (ref "S214") (pin "1") (pinfunction "1_1") (pintype "passive"))
    )
    (net (code "36") (name "Net-(D215-A)") (class "Default")
      (node (ref "D215") (pin "1") (pinfunction "A_1") (pintype "passive"))
      (node (ref "S215") (pin "1") (pinfunction "1_1") (pintype "passive"))
    )
    (net (code "37") (name "Net-(D216-A)") (class "Default")
      (node (ref "D216") (pin "1") (pinfunction "A_1") (pintype "passive"))
      (node (ref "S216") (pin "1") (pinfunction "1_1") (pintype "passive"))
    )
    (net (code "38") (name "Net-(D217-A)") (class "Default")
      (node (ref "D217") (pin "1") (pinfunction "A_1") (pintype "passive"))
      (node (ref "S217") (pin "1") (pinfunction "1_1") (pintype "passive"))
    )
    (net (code "39") (name "Net-(D218-A)") (class "Default")
      (node (ref "D218") (pin "1") (pinfunction "A_1") (pintype "passive"))
      (node (ref "S218") (pin "1") (pinfunction "1_1") (pintype "passive"))
    )
    (net (code "40") (name "Net-(D219-A)") (class "Default")
      (node (ref "D219") (pin "1") (pinfunction "A_1") (pintype "passive"))
      (node (ref "S219") (pin "1") (pinfunction "1_1") (pintype "passive"))
    )
    (net (code "41") (name "Net-(D220-A)") (class "Default")
      (node (ref "D220") (pin "1") (pinfunction "A_1") (pintype "passive"))
      (node (ref "S220") (pin "1") (pinfunction "1_1") (pintype "passive"))
    )
    (net (code "42") (name "Net-(D221-A)") (class "Default")
      (node (ref "D221") (pin "1") (pinfunction "A_1") (pintype "passive"))
      (node (ref "S221") (pin "1") (pinfunction "1_1") (pintype "passive"))
    )
    (net (code "43") (name "Net-(D222-A)") (class "Default")
      (node (ref "D222") (pin "1") (pinfunction "A_1") (pintype "passive"))
      (node (ref "S222") (pin "1") (pinfunction "1_1") (pintype "passive"))
    )
    (net (code "44") (name "Net-(D223-A)") (class "Default")
      (node (ref "D223") (pin "1") (pinfunction "A_1") (pintype "passive"))
      (node (ref "S223") (pin "1") (pinfunction "1_1") (pintype "passive"))
    )
    (net (code "45") (name "Net-(D224-A)") (class "Default")
      (node (ref "D224") (pin "1") (pinfunction "A_1") (pintype "passive"))
      (node (ref "S224") (pin "1") (pinfunction "1_1") (pintype "passive"))
    )
    (net (code "46") (name "Net-(D225-A)") (class "Default")
      (node (ref "D225") (pin "1") (pinfunction "A_1") (pintype "passive"))
      (node (ref "S225") (pin "1") (pinfunction "1_1") (pintype "passive"))
    )
    (net (code "47") (name "Net-(D226-A)") (class "Default")
      (node (ref "D226") (pin "1") (pinfunction "A_1") (pintype "passive"))
      (node (ref "S226") (pin "1") (pinfunction "1_1") (pintype "passive"))
    )
    (net (code "48") (name "Net-(D227-A)") (class "Default")
      (node (ref "D227") (pin "1") (pinfunction "A_1") (pintype "passive"))
      (node (ref "S227") (pin "1") (pinfunction "1_1") (pintype "passive"))
    )
    (net (code "49") (name "Net-(D228-A)") (class "Default")
      (node (ref "D228") (pin "1") (pinfunction "A_1") (pintype "passive"))
      (node (ref "S228") (pin "1") (pinfunction "1_1") (pintype "passive"))
    )
    (net (code "50") (name "Net-(D228_2-A)") (class "Default")
      (node (ref "D228_2") (pin "1") (pinfunction "A_1") (pintype "passive"))
      (node (ref "S228_2") (pin "1") (pinfunction "1_1") (pintype "passive"))
    )
    (net (code "51") (name "Net-(D229-A)") (class "Default")
      (node (ref "D229") (pin "1") (pinfunction "A_1") (pintype "passive"))
      (node (ref "S229") (pin "2") (pinfunction "2_2") (pintype "passive"))
      (node (ref "S229_1_ALPS") (pin "1") (pinfunction "1_1") (pintype "passive"))
    )
    (net (code "52") (name "Net-(D230-A)") (class "Default")
      (node (ref "D230") (pin "1") (pinfunction "A_1") (pintype "passive"))
      (node (ref "S230") (pin "1") (pinfunction "1_1") (pintype "passive"))
    )
    (net (code "53") (name "Net-(D231-A)") (class "Default")
      (node (ref "D231") (pin "1") (pinfunction "A_1") (pintype "passive"))
      (node (ref "S231") (pin "1") (pinfunction "1_1") (pintype "passive"))
    )
    (net (code "54") (name "Net-(D232-A)") (class "Default")
      (node (ref "D232") (pin "1") (pinfunction "A_1") (pintype "passive"))
      (node (ref "S232") (pin "1") (pinfunction "1_1") (pintype "passive"))
    )
    (net (code "55") (name "Net-(D233-A)") (class "Default")
      (node (ref "D233") (pin "1") (pinfunction "A_1") (pintype "passive"))
      (node (ref "S233") (pin "1") (pinfunction "1_1") (pintype "passive"))
    )
    (net (code "56") (name "Net-(D234-A)") (class "Default")
      (node (ref "D234") (pin "1") (pinfunction "A_1") (pintype "passive"))
      (node (ref "S234") (pin "1") (pinfunction "1_1") (pintype "passive"))
    )
    (net (code "57") (name "Net-(D235-A)") (class "Default")
      (node (ref "D235") (pin "1") (pinfunction "A_1") (pintype "passive"))
      (node (ref "S235") (pin "1") (pinfunction "1_1") (pintype "passive"))
    )
    (net (code "58") (name "Net-(D236-A)") (class "Default")
      (node (ref "D236") (pin "1") (pinfunction "A_1") (pintype "passive"))
      (node (ref "S236") (pin "1") (pinfunction "1_1") (pintype "passive"))
    )
    (net (code "59") (name "Net-(D237-A)") (class "Default")
      (node (ref "D237") (pin "1") (pinfunction "A_1") (pintype "passive"))
      (node (ref "S237") (pin "1") (pinfunction "1_1") (pintype "passive"))
    )
    (net (code "60") (name "Net-(D238-A)") (class "Default")
      (node (ref "D238") (pin "1") (pinfunction "A_1") (pintype "passive"))
      (node (ref "S238") (pin "1") (pinfunction "1_1") (pintype "passive"))
    )
    (net (code "61") (name "Net-(D239-A)") (class "Default")
      (node (ref "D239") (pin "1") (pinfunction "A_1") (pintype "passive"))
      (node (ref "S239") (pin "1") (pinfunction "1_1") (pintype "passive"))
    )
    (net (code "62") (name "Net-(D240-A)") (class "Default")
      (node (ref "D240") (pin "1") (pinfunction "A_1") (pintype "passive"))
      (node (ref "S240") (pin "1") (pinfunction "1_1") (pintype "passive"))
    )
    (net (code "63") (name "Net-(D241-A)") (class "Default")
      (node (ref "D241") (pin "1") (pinfunction "A_1") (pintype "passive"))
      (node (ref "S241") (pin "2") (pinfunction "2_2") (pintype "passive"))
    )
    (net (code "64") (name "Net-(D242-A)") (class "Default")
      (node (ref "D242") (pin "1") (pinfunction "A_1") (pintype "passive"))
      (node (ref "S242") (pin "1") (pinfunction "1_1") (pintype "passive"))
      (node (ref "S242_1_ALPS") (pin "2") (pinfunction "2_2") (pintype "passive"))
    )
    (net (code "65") (name "Net-(D243-A)") (class "Default")
      (node (ref "D243") (pin "1") (pinfunction "A_1") (pintype "passive"))
      (node (ref "S243") (pin "1") (pinfunction "1_1") (pintype "passive"))
    )
    (net (code "66") (name "Net-(D244-A)") (class "Default")
      (node (ref "D244") (pin "1") (pinfunction "A_1") (pintype "passive"))
      (node (ref "S244") (pin "2") (pinfunction "2_2") (pintype "passive"))
    )
    (net (code "67") (name "Net-(D245-A)") (class "Default")
      (node (ref "D245") (pin "1") (pinfunction "A_1") (pintype "passive"))
      (node (ref "S245") (pin "1") (pinfunction "1_1") (pintype "passive"))
    )
    (net (code "68") (name "Net-(D246-A)") (class "Default")
      (node (ref "D246") (pin "1") (pinfunction "A_1") (pintype "passive"))
      (node (ref "S246") (pin "1") (pinfunction "1_1") (pintype "passive"))
    )
    (net (code "69") (name "Net-(D247-A)") (class "Default")
      (node (ref "D247") (pin "1") (pinfunction "A_1") (pintype "passive"))
      (node (ref "S247") (pin "1") (pinfunction "1_1") (pintype "passive"))
    )
    (net (code "70") (name "Net-(D248-A)") (class "Default")
      (node (ref "D248") (pin "1") (pinfunction "A_1") (pintype "passive"))
      (node (ref "S248") (pin "1") (pinfunction "1_1") (pintype "passive"))
    )
    (net (code "71") (name "Net-(D249-A)") (class "Default")
      (node (ref "D249") (pin "1") (pinfunction "A_1") (pintype "passive"))
      (node (ref "S249") (pin "1") (pinfunction "1_1") (pintype "passive"))
    )
    (net (code "72") (name "Net-(D250-A)") (class "Default")
      (node (ref "D250") (pin "1") (pinfunction "A_1") (pintype "passive"))
      (node (ref "S250") (pin "1") (pinfunction "1_1") (pintype "passive"))
    )
    (net (code "73") (name "Net-(D251-A)") (class "Default")
      (node (ref "D251") (pin "1") (pinfunction "A_1") (pintype "passive"))
      (node (ref "S251") (pin "1") (pinfunction "1_1") (pintype "passive"))
    )
    (net (code "74") (name "Net-(D252-A)") (class "Default")
      (node (ref "D252") (pin "1") (pinfunction "A_1") (pintype "passive"))
      (node (ref "S252") (pin "1") (pinfunction "1_1") (pintype "passive"))
    )
    (net (code "75") (name "Net-(D253-A)") (class "Default")
      (node (ref "D253") (pin "1") (pinfunction "A_1") (pintype "passive"))
      (node (ref "S253") (pin "1") (pinfunction "1_1") (pintype "passive"))
    )
    (net (code "76") (name "Net-(D254-A)") (class "Default")
      (node (ref "D254") (pin "1") (pinfunction "A_1") (pintype "passive"))
      (node (ref "S254") (pin "1") (pinfunction "1_1") (pintype "passive"))
    )
    (net (code "77") (name "Net-(D255-A)") (class "Default")
      (node (ref "D255") (pin "1") (pinfunction "A_1") (pintype "passive"))
      (node (ref "S256") (pin "1") (pinfunction "1_1") (pintype "passive"))
    )
    (net (code "78") (name "Net-(D256-A)") (class "Default")
      (node (ref "D256") (pin "1") (pinfunction "A_1") (pintype "passive"))
      (node (ref "S269") (pin "1") (pinfunction "1_1") (pintype "passive"))
    )
    (net (code "79") (name "Net-(D257-A)") (class "Default")
      (node (ref "D257") (pin "1") (pinfunction "A_1") (pintype "passive"))
      (node (ref "S257") (pin "2") (pinfunction "2_2") (pintype "passive"))
    )
    (net (code "80") (name "Net-(D258-A)") (class "Default")
      (node (ref "D258") (pin "1") (pinfunction "A_1") (pintype "passive"))
      (node (ref "S258") (pin "1") (pinfunction "1_1") (pintype "passive"))
    )
    (net (code "81") (name "Net-(D259-A)") (class "Default")
      (node (ref "D259") (pin "1") (pinfunction "A_1") (pintype "passive"))
      (node (ref "S259") (pin "1") (pinfunction "1_1") (pintype "passive"))
    )
    (net (code "82") (name "Net-(D260-A)") (class "Default")
      (node (ref "D260") (pin "1") (pinfunction "A_1") (pintype "passive"))
      (node (ref "S260") (pin "1") (pinfunction "1_1") (pintype "passive"))
    )
    (net (code "83") (name "Net-(D262-A)") (class "Default")
      (node (ref "D262") (pin "1") (pinfunction "A_1") (pintype "passive"))
      (node (ref "S262") (pin "2") (pinfunction "2_2") (pintype "passive"))
      (node (ref "S262_1") (pin "2") (pinfunction "2_2") (pintype "passive"))
      (node (ref "S262_2") (pin "1") (pinfunction "1_1") (pintype "passive"))
    )
    (net (code "84") (name "Net-(D264-A)") (class "Default")
      (node (ref "D264") (pin "1") (pinfunction "A_1") (pintype "passive"))
      (node (ref "S264") (pin "1") (pinfunction "1_1") (pintype "passive"))
    )
    (net (code "85") (name "Net-(D265-A)") (class "Default")
      (node (ref "D265") (pin "1") (pinfunction "A_1") (pintype "passive"))
      (node (ref "S265") (pin "2") (pinfunction "2_2") (pintype "passive"))
    )
    (net (code "86") (name "Net-(D266-A)") (class "Default")
      (node (ref "D266") (pin "1") (pinfunction "A_1") (pintype "passive"))
      (node (ref "S266") (pin "1") (pinfunction "1_1") (pintype "passive"))
    )
    (net (code "87") (name "Net-(D270-A)") (class "Default")
      (node (ref "D270") (pin "1") (pinfunction "A_1") (pintype "passive"))
      (node (ref "S270") (pin "1") (pinfunction "1_1") (pintype "passive"))
    )
    (net (code "88") (name "Net-(D271-A)") (class "Default")
      (node (ref "D271") (pin "1") (pinfunction "A_1") (pintype "passive"))
      (node (ref "S271") (pin "1") (pinfunction "1_1") (pintype "passive"))
    )
    (net (code "89") (name "Net-(D272-A)") (class "Default")
      (node (ref "D272") (pin "1") (pinfunction "A_1") (pintype "passive"))
      (node (ref "S272") (pin "1") (pinfunction "1_1") (pintype "passive"))
    )
    (net (code "90") (name "Net-(D273-A)") (class "Default")
      (node (ref "D273") (pin "1") (pinfunction "A_1") (pintype "passive"))
      (node (ref "S273") (pin "1") (pinfunction "1_1") (pintype "passive"))
    )
    (net (code "91") (name "Net-(D274-A)") (class "Default")
      (node (ref "D274") (pin "1") (pinfunction "A_1") (pintype "passive"))
      (node (ref "S274") (pin "1") (pinfunction "1_1") (pintype "passive"))
    )
    (net (code "92") (name "Net-(D275-A)") (class "Default")
      (node (ref "D275") (pin "1") (pinfunction "A_1") (pintype "passive"))
      (node (ref "S275") (pin "1") (pinfunction "1_1") (pintype "passive"))
    )
    (net (code "93") (name "Net-(D276-A)") (class "Default")
      (node (ref "D276") (pin "1") (pinfunction "A_1") (pintype "passive"))
      (node (ref "S276") (pin "1") (pinfunction "1_1") (pintype "passive"))
    )
    (net (code "94") (name "Net-(D277-A)") (class "Default")
      (node (ref "D277") (pin "1") (pinfunction "A_1") (pintype "passive"))
      (node (ref "S277") (pin "1") (pinfunction "1_1") (pintype "passive"))
    )
    (net (code "95") (name "Net-(D278-A)") (class "Default")
      (node (ref "D278") (pin "1") (pinfunction "A_1") (pintype "passive"))
      (node (ref "S278") (pin "1") (pinfunction "1_1") (pintype "passive"))
    )
    (net (code "96") (name "Net-(D279-A)") (class "Default")
      (node (ref "D279") (pin "1") (pinfunction "A_1") (pintype "passive"))
      (node (ref "S279") (pin "1") (pinfunction "1_1") (pintype "passive"))
    )
    (net (code "97") (name "unconnected-(STAB1-Pad1)") (class "Default")
      (node (ref "STAB1") (pin "1") (pinfunction "1_1") (pintype "passive"))
    )
  )
)
